# CLAMP_SCH.net
KiCad netlist of a schematic drawn in Altium Designer
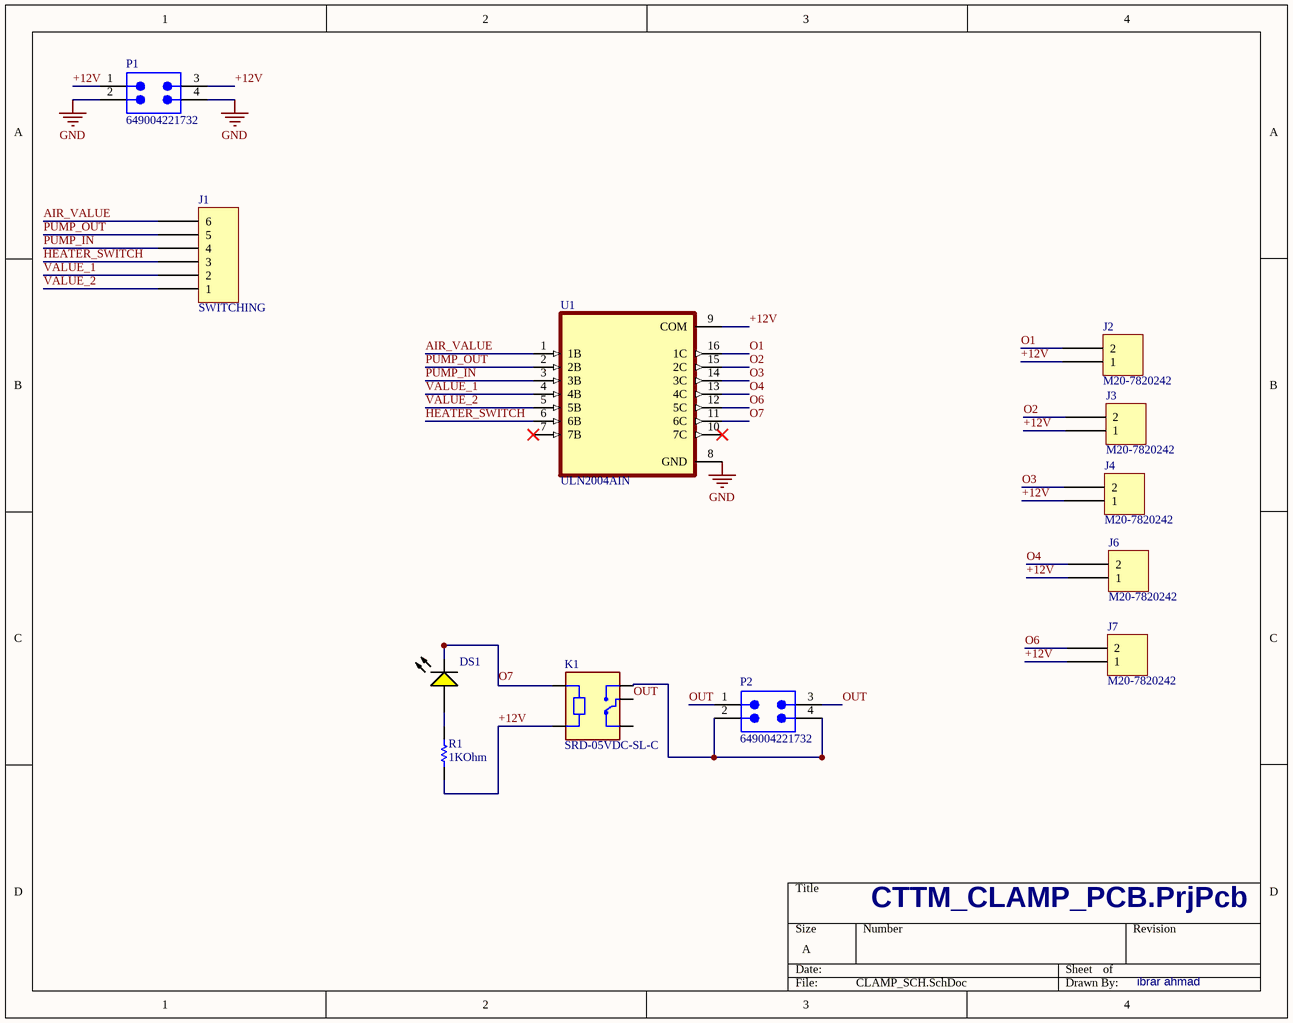
[diagram p0: CLAMP_SCH.SchDoc]

(export (version "E")
  (design (tool "Eeschema 10.0.6"))
  (components
    (comp (ref "DS1")
      (value "SML-LX1206YC-TR")
      (footprint "LUMX-SML-LX1206YC-TR_V")
      (description "Yellow LED, Water Clear Len, 585 nm, 2.1 V, -40 to 85 degC, 2-Pin SMD, RoHS, Tape and Reel")
      (fields (field (name "MANUFACTURER") "Lumex"))
      (libsource (lib "Altium Content Vault") (part "LED-YELLOW-AK-2"))
    )
    (comp (ref "J1")
      (value "SWITCHING")
      (footprint "MOLEX KK 0022272061")
      (description "CONN HEADER VERT 6POS 2.54MM")
      (fields (field (name "PART NUMBER") "0022272061") (field (name "MANUFACTURER") "Molex"))
      (libsource (lib "Celestial Altium Library - altium_library") (part "6 Pin"))
    )
    (comp (ref "J2")
      (value "M20-7820242")
      (footprint "HARWIN M20-7820245")
      (description "CONN RCPT 2POS 0.1 GOLD PCB")
      (fields (field (name "MANUFACTURER") "Harwin Inc."))
      (libsource (lib "Celestial Altium Library - altium_library") (part "2 Pin"))
    )
    (comp (ref "J3")
      (value "M20-7820242")
      (footprint "HARWIN M20-7820245")
      (description "CONN RCPT 2POS 0.1 GOLD PCB")
      (fields (field (name "MANUFACTURER") "Harwin Inc."))
      (libsource (lib "Celestial Altium Library - altium_library") (part "2 Pin"))
    )
    (comp (ref "J4")
      (value "M20-7820242")
      (footprint "HARWIN M20-7820245")
      (description "CONN RCPT 2POS 0.1 GOLD PCB")
      (fields (field (name "MANUFACTURER") "Harwin Inc."))
      (libsource (lib "Celestial Altium Library - altium_library") (part "2 Pin"))
    )
    (comp (ref "J6")
      (value "M20-7820242")
      (footprint "HARWIN M20-7820245")
      (description "CONN RCPT 2POS 0.1 GOLD PCB")
      (fields (field (name "MANUFACTURER") "Harwin Inc."))
      (libsource (lib "Celestial Altium Library - altium_library") (part "2 Pin"))
    )
    (comp (ref "J7")
      (value "M20-7820242")
      (footprint "HARWIN M20-7820245")
      (description "CONN RCPT 2POS 0.1 GOLD PCB")
      (fields (field (name "MANUFACTURER") "Harwin Inc."))
      (libsource (lib "Celestial Altium Library - altium_library") (part "2 Pin"))
    )
    (comp (ref "K1")
      (value "SRD-05VDC-SL-C")
      (footprint "RELAY_SRD-05VDC-SL-C")
      (fields (field (name "MF") "Songle Relay"))
      (libsource (lib "SRD-05VDC-SL-C") (part "SRD-05VDC-SL-C"))
    )
    (comp (ref "P1")
      (value "649004221732")
      (footprint "649004221732")
      (libsource (lib "Altium Content Vault") (part "Header_Male_2R_04P(A)"))
    )
    (comp (ref "P2")
      (value "649004221732")
      (footprint "649004221732")
      (libsource (lib "Altium Content Vault") (part "Header_Male_2R_04P(A)"))
    )
    (comp (ref "R1")
      (value "CRCW12061K00FKEA")
      (footprint "RESC3216X60X45ML15T20")
      (description "Chip Resistor, 1 KOhm, +/- 1%, 0.25 W, -55 to 155 degC, 1206 (3216 Metric), RoHS, Tape and Reel")
      (fields
        (field (name "MANUFACTURER") "Vishay Semiconductor")
        (field (name "TOLERANCE") "1%")
        (field (name "RESISTANCE") "1KOhm")
      )
      (libsource (lib "Altium Content Vault") (part "RES-2"))
    )
    (comp (ref "U1")
      (value "ULN2004AIN")
      (footprint "DIP794W45P254L1969H508Q16")
      (description "50-V, 7-ch darlington transistor array with 15-V input capability, -40 to 105C 16-PDIP -40 to 105")
      (fields (field (name "MF") "Texas Instruments"))
      (libsource (lib "ULN2004AIN") (part "ULN2004AIN"))
    )
  )
  (nets
    (net (code "1") (name "/+12V") (class "Default")
      (node (ref "J2") (pin "1") (pinfunction "1_1") (pintype "passive"))
      (node (ref "J3") (pin "1") (pinfunction "1_1") (pintype "passive"))
      (node (ref "J4") (pin "1") (pinfunction "1_1") (pintype "passive"))
      (node (ref "J6") (pin "1") (pinfunction "1_1") (pintype "passive"))
      (node (ref "J7") (pin "1") (pinfunction "1_1") (pintype "passive"))
      (node (ref "K1") (pin "A2") (pinfunction "A2_A2") (pintype "passive"))
      (node (ref "P1") (pin "1") (pinfunction "1_1") (pintype "passive"))
      (node (ref "P1") (pin "3") (pinfunction "3_3") (pintype "passive"))
      (node (ref "R1") (pin "1") (pinfunction "1_1") (pintype "passive"))
      (node (ref "U1") (pin "9") (pinfunction "COM_9") (pintype "power_in"))
    )
    (net (code "2") (name "/AIR_VALUE") (class "Default")
      (node (ref "J1") (pin "6") (pinfunction "6_6") (pintype "passive"))
      (node (ref "U1") (pin "1") (pinfunction "1B_1") (pintype "input"))
    )
    (net (code "3") (name "/HEATER_SWITCH") (class "Default")
      (node (ref "J1") (pin "3") (pinfunction "3_3") (pintype "passive"))
      (node (ref "U1") (pin "6") (pinfunction "6B_6") (pintype "input"))
    )
    (net (code "4") (name "/O1") (class "Default")
      (node (ref "J2") (pin "2") (pinfunction "2_2") (pintype "passive"))
      (node (ref "U1") (pin "16") (pinfunction "1C_16") (pintype "output"))
    )
    (net (code "5") (name "/O2") (class "Default")
      (node (ref "J3") (pin "2") (pinfunction "2_2") (pintype "passive"))
      (node (ref "U1") (pin "15") (pinfunction "2C_15") (pintype "output"))
    )
    (net (code "6") (name "/O3") (class "Default")
      (node (ref "J4") (pin "2") (pinfunction "2_2") (pintype "passive"))
      (node (ref "U1") (pin "14") (pinfunction "3C_14") (pintype "output"))
    )
    (net (code "7") (name "/O4") (class "Default")
      (node (ref "J6") (pin "2") (pinfunction "2_2") (pintype "passive"))
      (node (ref "U1") (pin "13") (pinfunction "4C_13") (pintype "output"))
    )
    (net (code "8") (name "/O6") (class "Default")
      (node (ref "J7") (pin "2") (pinfunction "2_2") (pintype "passive"))
      (node (ref "U1") (pin "12") (pinfunction "5C_12") (pintype "output"))
    )
    (net (code "9") (name "/O7") (class "Default")
      (node (ref "DS1") (pin "2") (pinfunction "K_2") (pintype "passive"))
      (node (ref "K1") (pin "A1") (pinfunction "A1_A1") (pintype "passive"))
      (node (ref "U1") (pin "11") (pinfunction "6C_11") (pintype "output"))
    )
    (net (code "10") (name "/OUT") (class "Default")
      (node (ref "K1") (pin "COM") (pinfunction "COM_COM") (pintype "passive"))
      (node (ref "P2") (pin "1") (pinfunction "1_1") (pintype "passive"))
      (node (ref "P2") (pin "3") (pinfunction "3_3") (pintype "passive"))
    )
    (net (code "11") (name "/PUMP_IN") (class "Default")
      (node (ref "J1") (pin "4") (pinfunction "4_4") (pintype "passive"))
      (node (ref "U1") (pin "3") (pinfunction "3B_3") (pintype "input"))
    )
    (net (code "12") (name "/PUMP_OUT") (class "Default")
      (node (ref "J1") (pin "5") (pinfunction "5_5") (pintype "passive"))
      (node (ref "U1") (pin "2") (pinfunction "2B_2") (pintype "input"))
    )
    (net (code "13") (name "/VALUE_1") (class "Default")
      (node (ref "J1") (pin "2") (pinfunction "2_2") (pintype "passive"))
      (node (ref "U1") (pin "4") (pinfunction "4B_4") (pintype "input"))
    )
    (net (code "14") (name "/VALUE_2") (class "Default")
      (node (ref "J1") (pin "1") (pinfunction "1_1") (pintype "passive"))
      (node (ref "U1") (pin "5") (pinfunction "5B_5") (pintype "input"))
    )
    (net (code "15") (name "GND") (class "Default")
      (node (ref "P1") (pin "2") (pinfunction "2_2") (pintype "passive"))
      (node (ref "P1") (pin "4") (pinfunction "4_4") (pintype "passive"))
      (node (ref "U1") (pin "8") (pinfunction "GND_8") (pintype "power_in"))
    )
    (net (code "16") (name "Net-(DS1-A)") (class "Default")
      (node (ref "DS1") (pin "1") (pinfunction "A_1") (pintype "passive"))
      (node (ref "R1") (pin "2") (pinfunction "2_2") (pintype "passive"))
    )
    (net (code "17") (name "Net-(K1-PadNO)") (class "Default")
      (node (ref "K1") (pin "NO") (pinfunction "NO_NO") (pintype "passive"))
      (node (ref "P2") (pin "2") (pinfunction "2_2") (pintype "passive"))
      (node (ref "P2") (pin "4") (pinfunction "4_4") (pintype "passive"))
    )
    (net (code "18") (name "unconnected-(K1-PadNC)") (class "Default")
      (node (ref "K1") (pin "NC") (pinfunction "NC_NC") (pintype "passive"))
    )
    (net (code "19") (name "unconnected-(U1-7B-Pad7)") (class "Default")
      (node (ref "U1") (pin "7") (pinfunction "7B_7") (pintype "input+no_connect"))
    )
    (net (code "20") (name "unconnected-(U1-7C-Pad10)") (class "Default")
      (node (ref "U1") (pin "10") (pinfunction "7C_10") (pintype "output+no_connect"))
    )
  )
)
